# Qwiic_RFID_-_IDXXLA.net
KiCad netlist of a schematic drawn in EAGLE
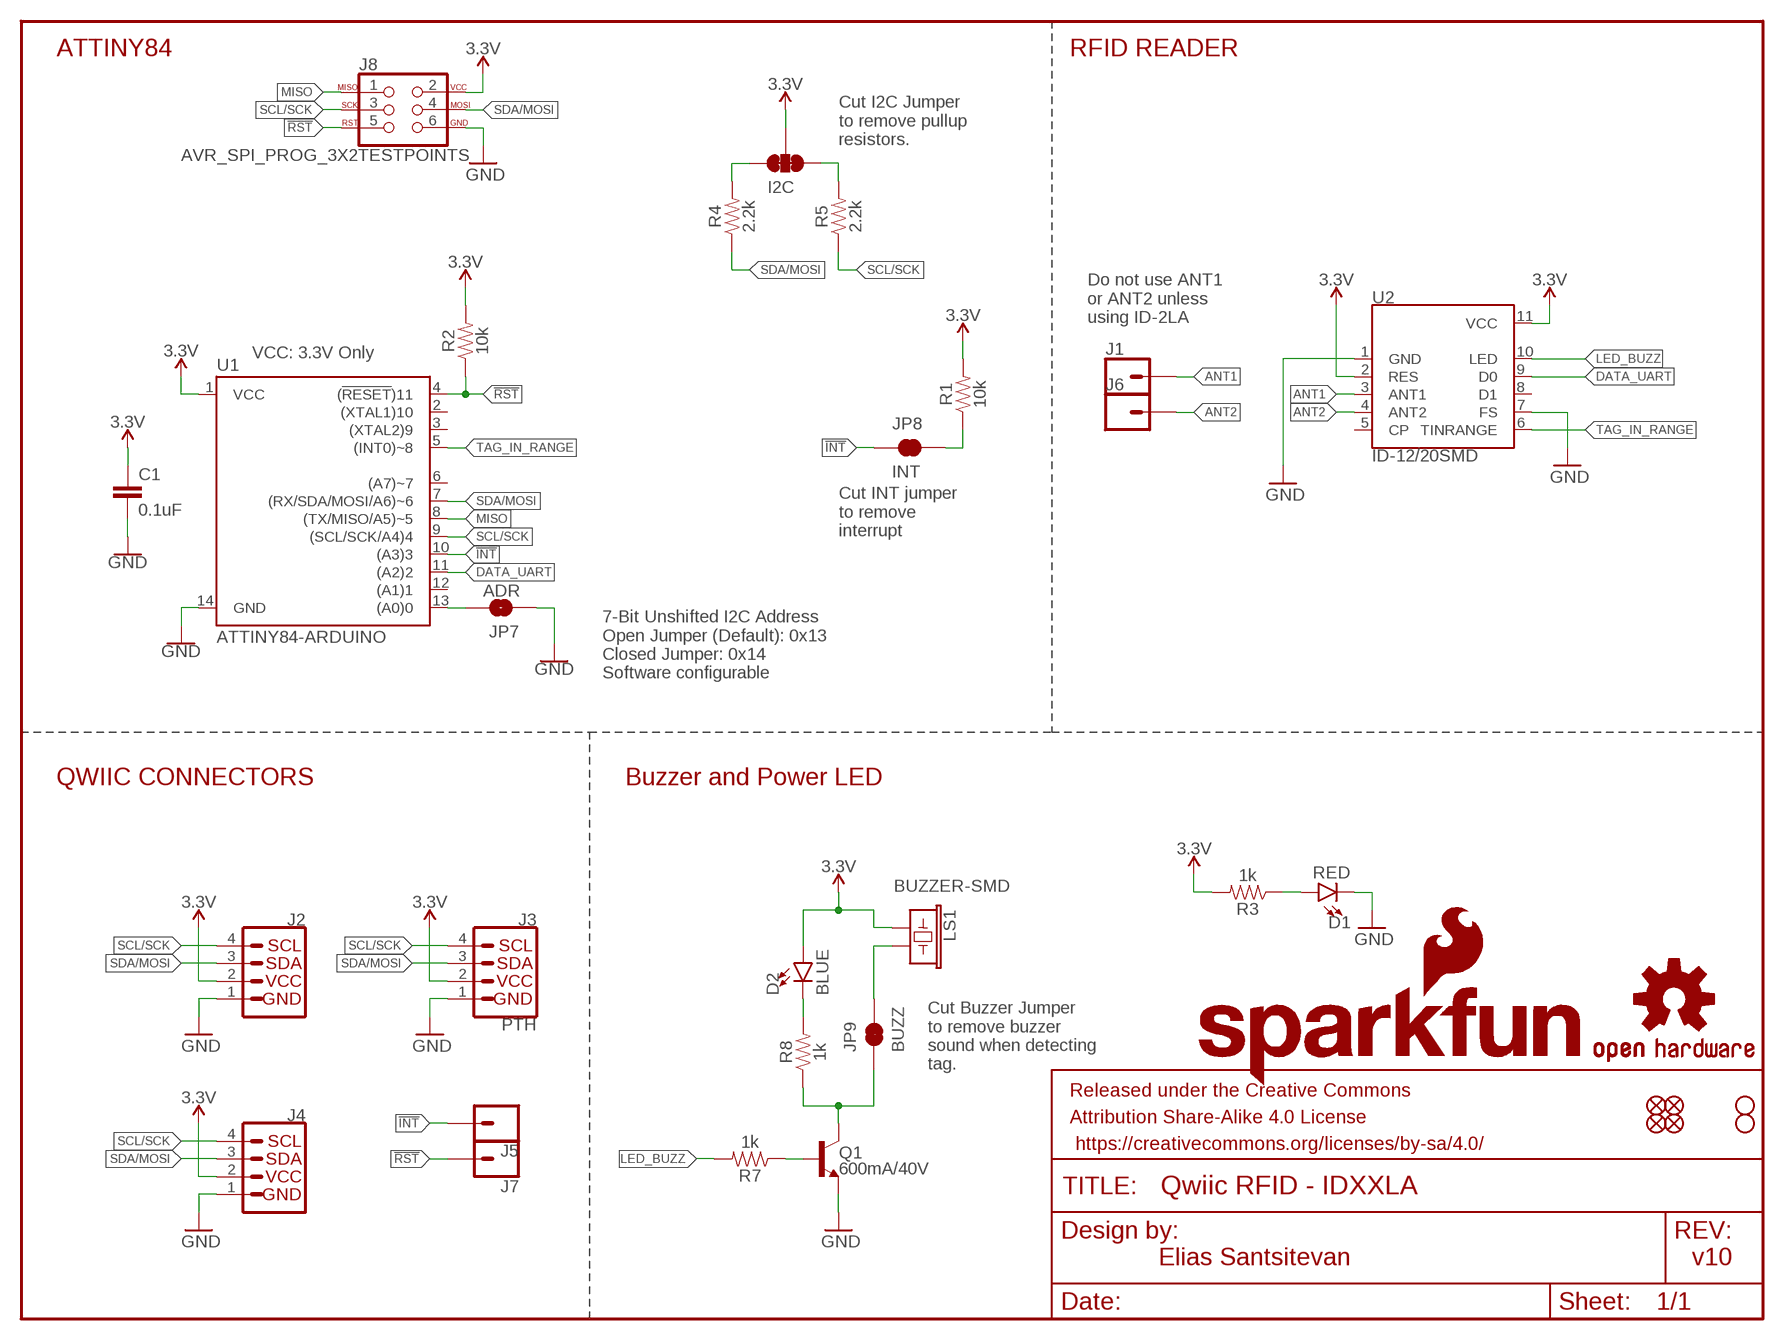
[diagram p0: schematic, sheet 1]

(export (version "E")
  (design (tool "Eeschema 10.0.6"))
  (components
    (comp (ref "C1")
      (value "0.1uF")
      (footprint "eagle-import:0603")
      (libsource (lib "eagle-import") (part "0.1UF-0603-25V-(+80/-20%)"))
    )
    (comp (ref "D1")
      (value "RED")
      (footprint "eagle-import:LED-0603")
      (libsource (lib "eagle-import") (part "LED-RED0603"))
    )
    (comp (ref "D2")
      (value "BLUE")
      (footprint "eagle-import:LED-0603")
      (libsource (lib "eagle-import") (part "LED-BLUE0603"))
    )
    (comp (ref "FRAME1")
      (value "FRAME-LETTER")
      (footprint "eagle-import:CREATIVE_COMMONS")
      (libsource (lib "eagle-import") (part "FRAME-LETTER"))
    )
    (comp (ref "I2C")
      (value "JUMPER-SMT_3_2-NC_TRACE_SILK")
      (footprint "eagle-import:SMT-JUMPER_3_2-NC_TRACE_SILK")
      (libsource (lib "eagle-import") (part "JUMPER-SMT_3_2-NC_TRACE_SILK"))
    )
    (comp (ref "J1")
      (value "CONN_01PTH_NO_SILK_YES_STOP")
      (footprint "eagle-import:1X01_NO_SILK")
      (libsource (lib "eagle-import") (part "CONN_01PTH_NO_SILK_YES_STOP"))
    )
    (comp (ref "J2")
      (value "QWIIC_CONNECTORJS-1MM")
      (footprint "eagle-import:1X04_1MM_RA")
      (libsource (lib "eagle-import") (part "QWIIC_CONNECTORJS-1MM"))
    )
    (comp (ref "J3")
      (value "PTH")
      (footprint "eagle-import:1X04_NO_SILK")
      (libsource (lib "eagle-import") (part "I2C_STANDARD_NO_SILK"))
    )
    (comp (ref "J4")
      (value "QWIIC_CONNECTORJS-1MM")
      (footprint "eagle-import:1X04_1MM_RA")
      (libsource (lib "eagle-import") (part "QWIIC_CONNECTORJS-1MM"))
    )
    (comp (ref "J5")
      (value "CONN_01PTH_NO_SILK_YES_STOP")
      (footprint "eagle-import:1X01_NO_SILK")
      (libsource (lib "eagle-import") (part "CONN_01PTH_NO_SILK_YES_STOP"))
    )
    (comp (ref "J6")
      (value "CONN_01PTH_NO_SILK_YES_STOP")
      (footprint "eagle-import:1X01_NO_SILK")
      (libsource (lib "eagle-import") (part "CONN_01PTH_NO_SILK_YES_STOP"))
    )
    (comp (ref "J7")
      (value "CONN_01PTH_NO_SILK_YES_STOP")
      (footprint "eagle-import:1X01_NO_SILK")
      (libsource (lib "eagle-import") (part "CONN_01PTH_NO_SILK_YES_STOP"))
    )
    (comp (ref "J8")
      (value "AVR_SPI_PROG_3X2TESTPOINTS")
      (footprint "eagle-import:2X3_TEST_POINTS")
      (libsource (lib "eagle-import") (part "AVR_SPI_PROG_3X2TESTPOINTS"))
    )
    (comp (ref "JP1")
      (value "FIDUCIALUFIDUCIAL")
      (footprint "eagle-import:MICRO-FIDUCIAL")
      (libsource (lib "eagle-import") (part "FIDUCIALUFIDUCIAL"))
    )
    (comp (ref "JP2")
      (value "FIDUCIALUFIDUCIAL")
      (footprint "eagle-import:MICRO-FIDUCIAL")
      (libsource (lib "eagle-import") (part "FIDUCIALUFIDUCIAL"))
    )
    (comp (ref "JP3")
      (value "STAND-OFF")
      (footprint "eagle-import:STAND-OFF")
      (libsource (lib "eagle-import") (part "STAND-OFF"))
    )
    (comp (ref "JP4")
      (value "STAND-OFF")
      (footprint "eagle-import:STAND-OFF")
      (libsource (lib "eagle-import") (part "STAND-OFF"))
    )
    (comp (ref "JP5")
      (value "FIDUCIALUFIDUCIAL")
      (footprint "eagle-import:MICRO-FIDUCIAL")
      (libsource (lib "eagle-import") (part "FIDUCIALUFIDUCIAL"))
    )
    (comp (ref "JP6")
      (value "FIDUCIALUFIDUCIAL")
      (footprint "eagle-import:MICRO-FIDUCIAL")
      (libsource (lib "eagle-import") (part "FIDUCIALUFIDUCIAL"))
    )
    (comp (ref "JP7")
      (value "ADR")
      (footprint "eagle-import:SMT-JUMPER_2_NO_SILK")
      (libsource (lib "eagle-import") (part "JUMPER-SMT_2_NO_SILK"))
    )
    (comp (ref "JP8")
      (value "INT")
      (footprint "eagle-import:SMT-JUMPER_2_NC_TRACE_SILK")
      (libsource (lib "eagle-import") (part "JUMPER-SMT_2_NC_TRACE_SILK"))
    )
    (comp (ref "JP9")
      (value "BUZZ")
      (footprint "eagle-import:SMT-JUMPER_2_NC_TRACE_SILK")
      (libsource (lib "eagle-import") (part "JUMPER-SMT_2_NC_TRACE_SILK"))
    )
    (comp (ref "LOGO1")
      (value "OSHW-LOGOMINI")
      (footprint "eagle-import:OSHW-LOGO-MINI")
      (libsource (lib "eagle-import") (part "OSHW-LOGOMINI"))
    )
    (comp (ref "LOGO3")
      (value "SFE_LOGO_NAME_FLAME.1_INCH")
      (footprint "eagle-import:SFE_LOGO_NAME_FLAME_.1")
      (libsource (lib "eagle-import") (part "SFE_LOGO_NAME_FLAME.1_INCH"))
    )
    (comp (ref "LS1")
      (value "BUZZER-SMD")
      (footprint "eagle-import:BUZZER-CCV")
      (libsource (lib "eagle-import") (part "BUZZER-SMD"))
    )
    (comp (ref "Q1")
      (value "600mA/40V")
      (footprint "eagle-import:SOT23-3")
      (libsource (lib "eagle-import") (part "TRANS_NPN-MMBT2222AL"))
    )
    (comp (ref "R1")
      (value "10k")
      (footprint "eagle-import:0603")
      (libsource (lib "eagle-import") (part "10KOHM-0603-1/10W-1%"))
    )
    (comp (ref "R2")
      (value "10k")
      (footprint "eagle-import:0603")
      (libsource (lib "eagle-import") (part "10KOHM-0603-1/10W-1%"))
    )
    (comp (ref "R3")
      (value "1k")
      (footprint "eagle-import:0603")
      (libsource (lib "eagle-import") (part "1KOHM-0603-1/10W-1%"))
    )
    (comp (ref "R4")
      (value "2.2k")
      (footprint "eagle-import:0603")
      (libsource (lib "eagle-import") (part "2.2KOHM-0603-1/10W-1%"))
    )
    (comp (ref "R5")
      (value "2.2k")
      (footprint "eagle-import:0603")
      (libsource (lib "eagle-import") (part "2.2KOHM-0603-1/10W-1%"))
    )
    (comp (ref "R7")
      (value "1k")
      (footprint "eagle-import:0603")
      (libsource (lib "eagle-import") (part "1KOHM-0603-1/10W-1%"))
    )
    (comp (ref "R8")
      (value "1k")
      (footprint "eagle-import:0603")
      (libsource (lib "eagle-import") (part "1KOHM-0603-1/10W-1%"))
    )
    (comp (ref "U1")
      (value "ATTINY84-ARDUINO")
      (footprint "eagle-import:SO14")
      (libsource (lib "eagle-import") (part "ATTINY84-ARDUINO"))
    )
    (comp (ref "U2")
      (value "ID-12/20SMD")
      (footprint "eagle-import:ID-12_SMD")
      (libsource (lib "eagle-import") (part "ID-12/20SMD"))
    )
  )
  (nets
    (net (code "1") (name "/~{INT}") (class "Default")
      (node (ref "J5") (pin "1") (pinfunction "1_1") (pintype "passive"))
      (node (ref "JP8") (pin "1") (pinfunction "1_1") (pintype "passive"))
      (node (ref "U1") (pin "10") (pinfunction "(A3)3_10") (pintype "bidirectional"))
    )
    (net (code "2") (name "/~{RST}") (class "Default")
      (node (ref "J7") (pin "1") (pinfunction "1_1") (pintype "passive"))
      (node (ref "J8") (pin "5") (pinfunction "5_5") (pintype "passive"))
      (node (ref "R2") (pin "1") (pinfunction "1_1") (pintype "passive"))
      (node (ref "U1") (pin "4") (pinfunction "(~{RESET})11_4") (pintype "bidirectional"))
    )
    (net (code "3") (name "3.3V") (class "Default")
      (node (ref "C1") (pin "1") (pinfunction "1_1") (pintype "passive"))
      (node (ref "D2") (pin "A") (pinfunction "A_A") (pintype "passive"))
      (node (ref "I2C") (pin "2") (pinfunction "2_2") (pintype "passive"))
      (node (ref "J2") (pin "2") (pinfunction "2_2") (pintype "power_in"))
      (node (ref "J3") (pin "2") (pinfunction "VCC_2") (pintype "power_in"))
      (node (ref "J4") (pin "2") (pinfunction "2_2") (pintype "power_in"))
      (node (ref "J8") (pin "2") (pinfunction "2_2") (pintype "passive"))
      (node (ref "LS1") (pin "+") (pinfunction "1_+") (pintype "passive"))
      (node (ref "R1") (pin "2") (pinfunction "2_2") (pintype "passive"))
      (node (ref "R2") (pin "2") (pinfunction "2_2") (pintype "passive"))
      (node (ref "R3") (pin "2") (pinfunction "2_2") (pintype "passive"))
      (node (ref "U1") (pin "1") (pinfunction "VCC_1") (pintype "bidirectional"))
      (node (ref "U2") (pin "11") (pinfunction "VCC_11") (pintype "bidirectional"))
      (node (ref "U2") (pin "2") (pinfunction "RES_2") (pintype "bidirectional"))
    )
    (net (code "4") (name "ANT1") (class "Default")
      (node (ref "J1") (pin "1") (pinfunction "1_1") (pintype "passive"))
      (node (ref "U2") (pin "3") (pinfunction "ANT1_3") (pintype "bidirectional"))
    )
    (net (code "5") (name "ANT2") (class "Default")
      (node (ref "J6") (pin "1") (pinfunction "1_1") (pintype "passive"))
      (node (ref "U2") (pin "4") (pinfunction "ANT2_4") (pintype "bidirectional"))
    )
    (net (code "6") (name "DATA_UART") (class "Default")
      (node (ref "U1") (pin "11") (pinfunction "(A2)2_11") (pintype "bidirectional"))
      (node (ref "U2") (pin "9") (pinfunction "D0_9") (pintype "bidirectional"))
    )
    (net (code "7") (name "GND") (class "Default")
      (node (ref "C1") (pin "2") (pinfunction "2_2") (pintype "passive"))
      (node (ref "D1") (pin "C") (pinfunction "C_C") (pintype "passive"))
      (node (ref "J2") (pin "1") (pinfunction "1_1") (pintype "power_in"))
      (node (ref "J3") (pin "1") (pinfunction "GND_1") (pintype "power_in"))
      (node (ref "J4") (pin "1") (pinfunction "1_1") (pintype "power_in"))
      (node (ref "J8") (pin "6") (pinfunction "6_6") (pintype "passive"))
      (node (ref "JP7") (pin "1") (pinfunction "1_1") (pintype "passive"))
      (node (ref "Q1") (pin "2") (pinfunction "E_2") (pintype "passive"))
      (node (ref "U1") (pin "14") (pinfunction "GND_14") (pintype "bidirectional"))
      (node (ref "U2") (pin "1") (pinfunction "GND_1") (pintype "bidirectional"))
      (node (ref "U2") (pin "7") (pinfunction "FS_7") (pintype "bidirectional"))
    )
    (net (code "8") (name "LED_BUZZ") (class "Default")
      (node (ref "R7") (pin "2") (pinfunction "2_2") (pintype "passive"))
      (node (ref "U2") (pin "10") (pinfunction "LED_10") (pintype "bidirectional"))
    )
    (net (code "9") (name "MISO") (class "Default")
      (node (ref "J8") (pin "1") (pinfunction "1_1") (pintype "passive"))
      (node (ref "U1") (pin "8") (pinfunction "(TX/MISO/A5)~{5}_8") (pintype "bidirectional"))
    )
    (net (code "10") (name "Net-(D1-PadA)") (class "Default")
      (node (ref "D1") (pin "A") (pinfunction "A_A") (pintype "passive"))
      (node (ref "R3") (pin "1") (pinfunction "1_1") (pintype "passive"))
    )
    (net (code "11") (name "Net-(D2-PadC)") (class "Default")
      (node (ref "D2") (pin "C") (pinfunction "C_C") (pintype "passive"))
      (node (ref "R8") (pin "2") (pinfunction "2_2") (pintype "passive"))
    )
    (net (code "12") (name "Net-(I2C-Pad1)") (class "Default")
      (node (ref "I2C") (pin "1") (pinfunction "1_1") (pintype "passive"))
      (node (ref "R5") (pin "2") (pinfunction "2_2") (pintype "passive"))
    )
    (net (code "13") (name "Net-(I2C-Pad3)") (class "Default")
      (node (ref "I2C") (pin "3") (pinfunction "3_3") (pintype "passive"))
      (node (ref "R4") (pin "2") (pinfunction "2_2") (pintype "passive"))
    )
    (net (code "14") (name "Net-(JP8-Pad2)") (class "Default")
      (node (ref "JP8") (pin "2") (pinfunction "2_2") (pintype "passive"))
      (node (ref "R1") (pin "1") (pinfunction "1_1") (pintype "passive"))
    )
    (net (code "15") (name "Net-(LS1-2)") (class "Default")
      (node (ref "JP9") (pin "2") (pinfunction "2_2") (pintype "passive"))
      (node (ref "LS1") (pin "-") (pinfunction "2_-") (pintype "passive"))
    )
    (net (code "16") (name "Net-(Q1-B)") (class "Default")
      (node (ref "Q1") (pin "1") (pinfunction "B_1") (pintype "passive"))
      (node (ref "R7") (pin "1") (pinfunction "1_1") (pintype "passive"))
    )
    (net (code "17") (name "Net-(Q1-C)") (class "Default")
      (node (ref "JP9") (pin "1") (pinfunction "1_1") (pintype "passive"))
      (node (ref "Q1") (pin "3") (pinfunction "C_3") (pintype "passive"))
      (node (ref "R8") (pin "1") (pinfunction "1_1") (pintype "passive"))
    )
    (net (code "18") (name "Net-(U1-(A0)0)") (class "Default")
      (node (ref "JP7") (pin "2") (pinfunction "2_2") (pintype "passive"))
      (node (ref "U1") (pin "13") (pinfunction "(A0)0_13") (pintype "bidirectional"))
    )
    (net (code "19") (name "SCL{slash}SCK") (class "Default")
      (node (ref "J2") (pin "4") (pinfunction "4_4") (pintype "passive"))
      (node (ref "J3") (pin "4") (pinfunction "SCL_4") (pintype "passive"))
      (node (ref "J4") (pin "4") (pinfunction "4_4") (pintype "passive"))
      (node (ref "J8") (pin "3") (pinfunction "3_3") (pintype "passive"))
      (node (ref "R5") (pin "1") (pinfunction "1_1") (pintype "passive"))
      (node (ref "U1") (pin "9") (pinfunction "(SCL/SCK/A4)4_9") (pintype "bidirectional"))
    )
    (net (code "20") (name "SDA{slash}MOSI") (class "Default")
      (node (ref "J2") (pin "3") (pinfunction "3_3") (pintype "passive"))
      (node (ref "J3") (pin "3") (pinfunction "SDA_3") (pintype "passive"))
      (node (ref "J4") (pin "3") (pinfunction "3_3") (pintype "passive"))
      (node (ref "J8") (pin "4") (pinfunction "4_4") (pintype "passive"))
      (node (ref "R4") (pin "1") (pinfunction "1_1") (pintype "passive"))
      (node (ref "U1") (pin "7") (pinfunction "(RX/SDA/MOSI/A6)~{6}_7") (pintype "bidirectional"))
    )
    (net (code "21") (name "TAG_IN_RANGE") (class "Default")
      (node (ref "U1") (pin "5") (pinfunction "(INT0)~{8}_5") (pintype "bidirectional"))
      (node (ref "U2") (pin "6") (pinfunction "TINRANGE_6") (pintype "bidirectional"))
    )
    (net (code "22") (name "unconnected-(U1-(A1)1-Pad12)") (class "Default")
      (node (ref "U1") (pin "12") (pinfunction "(A1)1_12") (pintype "bidirectional"))
    )
    (net (code "23") (name "unconnected-(U1-(A7)~{7}-Pad6)") (class "Default")
      (node (ref "U1") (pin "6") (pinfunction "(A7)~{7}_6") (pintype "bidirectional"))
    )
    (net (code "24") (name "unconnected-(U1-(XTAL1)10-Pad2)") (class "Default")
      (node (ref "U1") (pin "2") (pinfunction "(XTAL1)10_2") (pintype "bidirectional"))
    )
    (net (code "25") (name "unconnected-(U1-(XTAL2)9-Pad3)") (class "Default")
      (node (ref "U1") (pin "3") (pinfunction "(XTAL2)9_3") (pintype "bidirectional"))
    )
    (net (code "26") (name "unconnected-(U2-CP-Pad5)") (class "Default")
      (node (ref "U2") (pin "5") (pinfunction "CP_5") (pintype "bidirectional"))
    )
    (net (code "27") (name "unconnected-(U2-D1-Pad8)") (class "Default")
      (node (ref "U2") (pin "8") (pinfunction "D1_8") (pintype "bidirectional"))
    )
  )
)
